# rtmi.net
KiCad netlist of a schematic drawn in EAGLE
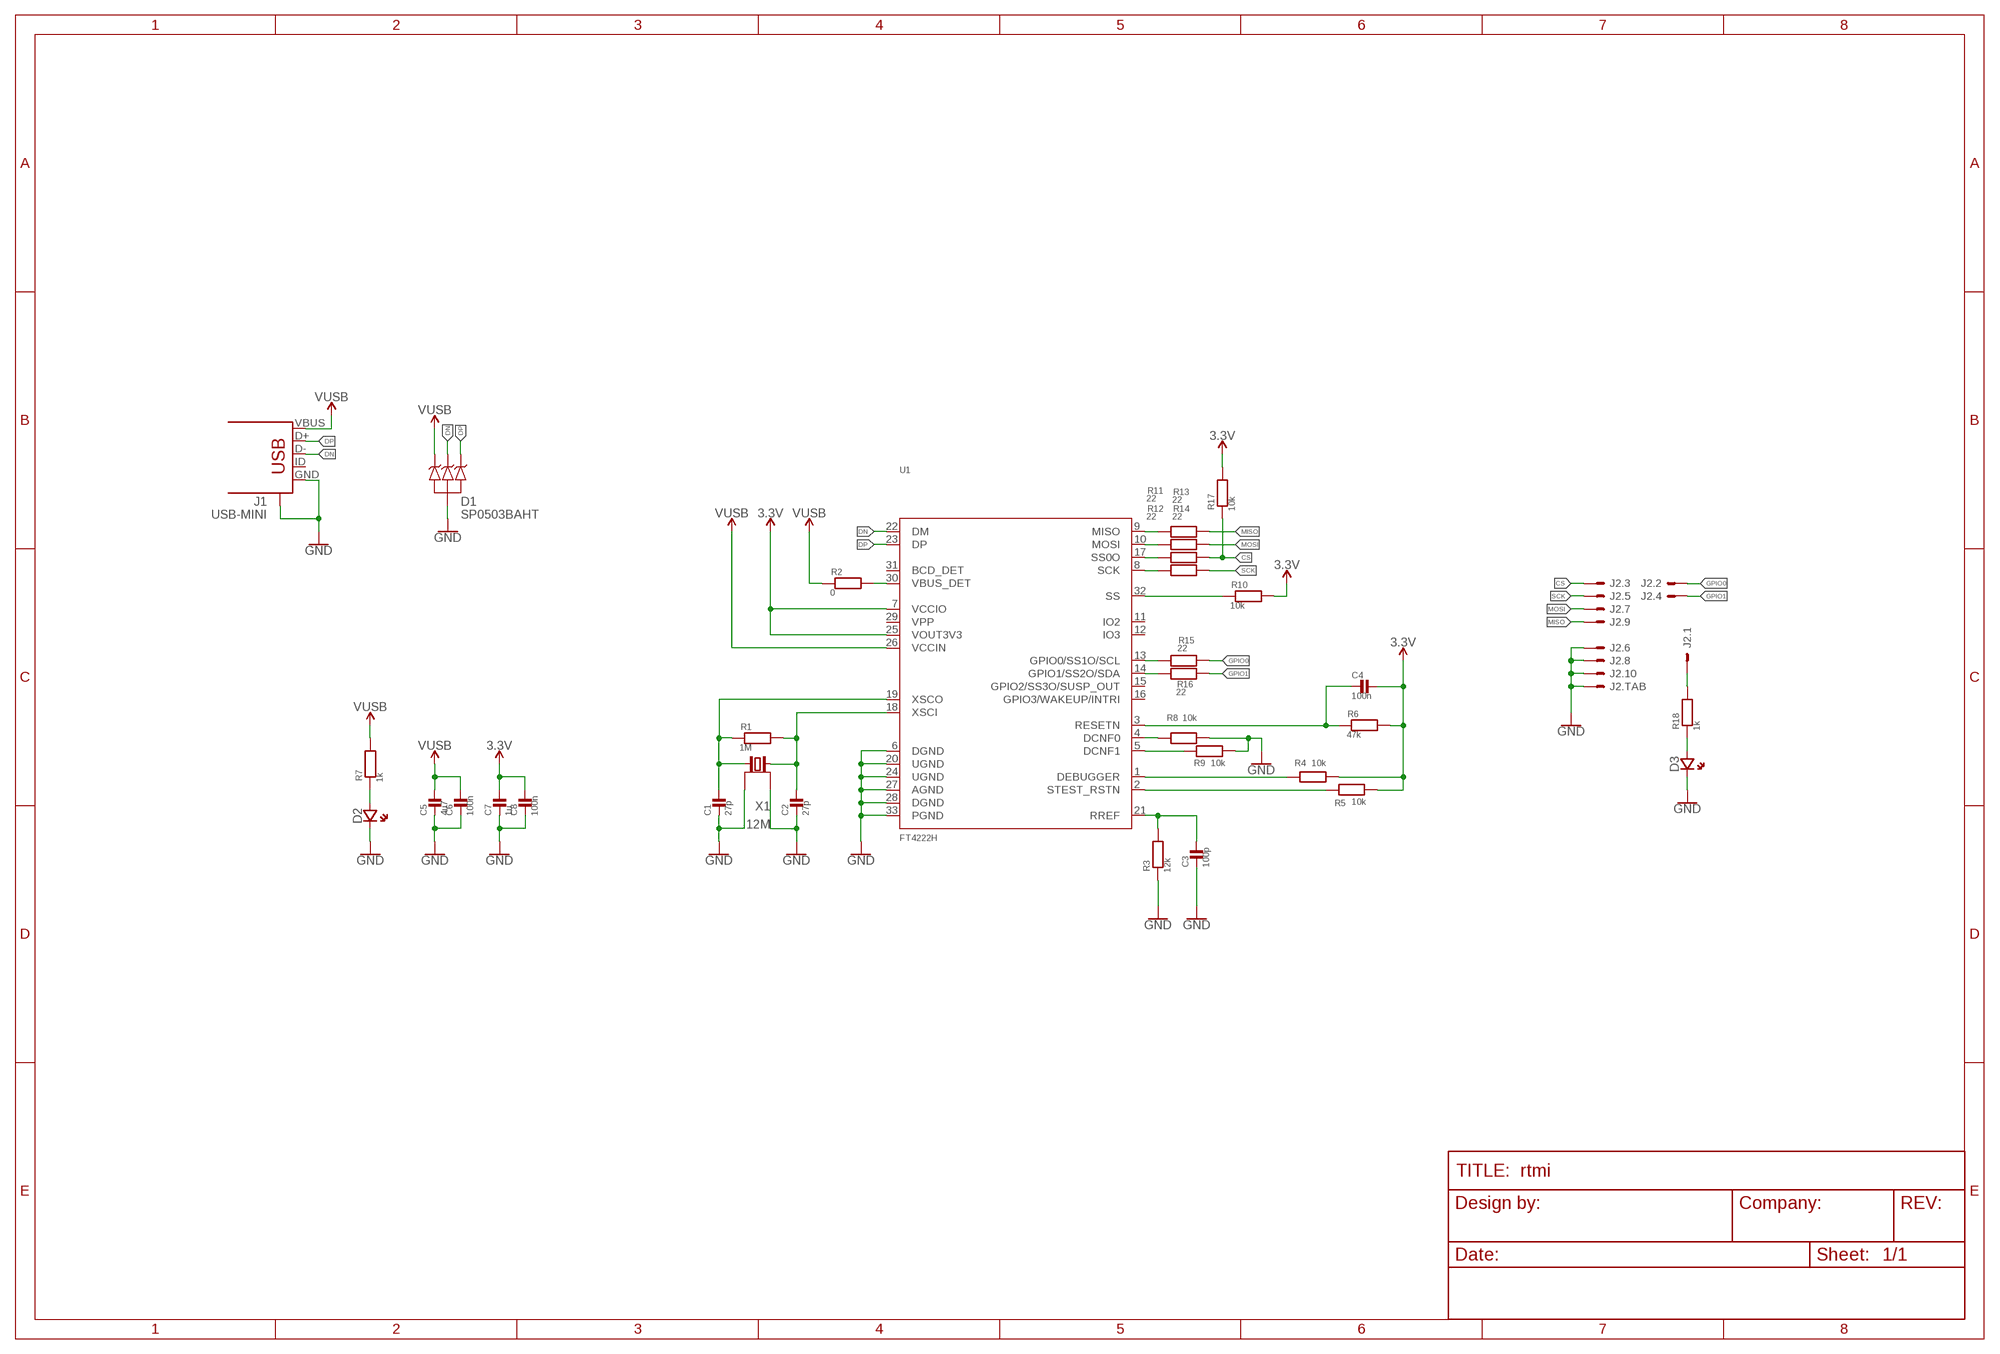
[diagram p0: schematic, sheet 1]

(export (version "E")
  (design (tool "Eeschema 10.0.6"))
  (components
    (comp (ref "C1")
      (value "27p")
      (footprint "eagle-import:0603_WAVE")
      (libsource (lib "eagle-import") (part "MLCC0603"))
    )
    (comp (ref "C2")
      (value "27p")
      (footprint "eagle-import:0603_WAVE")
      (libsource (lib "eagle-import") (part "MLCC0603"))
    )
    (comp (ref "C3")
      (value "100p")
      (footprint "eagle-import:0603_WAVE")
      (libsource (lib "eagle-import") (part "MLCC0603"))
    )
    (comp (ref "C4")
      (value "100n")
      (footprint "eagle-import:0603_WAVE")
      (libsource (lib "eagle-import") (part "MLCC0603"))
    )
    (comp (ref "C5")
      (value "4u7")
      (footprint "eagle-import:0603_WAVE")
      (libsource (lib "eagle-import") (part "MLCC0603"))
    )
    (comp (ref "C6")
      (value "100n")
      (footprint "eagle-import:0603_WAVE")
      (libsource (lib "eagle-import") (part "MLCC0603"))
    )
    (comp (ref "C7")
      (value "1u")
      (footprint "eagle-import:0603_WAVE")
      (libsource (lib "eagle-import") (part "MLCC0603"))
    )
    (comp (ref "C8")
      (value "100n")
      (footprint "eagle-import:0603_WAVE")
      (libsource (lib "eagle-import") (part "MLCC0603"))
    )
    (comp (ref "D1")
      (value "SP0503BAHT")
      (footprint "eagle-import:SOT143")
      (libsource (lib "eagle-import") (part "SP0503BAHT"))
    )
    (comp (ref "D2")
      (value "LED0603")
      (footprint "eagle-import:CHIPLED_0603")
      (libsource (lib "eagle-import") (part "LED0603"))
    )
    (comp (ref "D3")
      (value "LED0603")
      (footprint "eagle-import:CHIPLED_0603")
      (libsource (lib "eagle-import") (part "LED0603"))
    )
    (comp (ref "J1")
      (value "USB-MINI")
      (footprint "eagle-import:USB-MINI-SMD")
      (libsource (lib "eagle-import") (part "USB-MINI"))
    )
    (comp (ref "J2")
      (value "F20F-10DP-1V")
      (footprint "eagle-import:F20F-10DP-1V")
      (libsource (lib "eagle-import") (part "F20F-10DP-1V"))
    )
    (comp (ref "R1")
      (value "1M")
      (footprint "eagle-import:0603_WAVE")
      (libsource (lib "eagle-import") (part "RESISTOR0603"))
    )
    (comp (ref "R2")
      (value "0")
      (footprint "eagle-import:0603_WAVE")
      (libsource (lib "eagle-import") (part "RESISTOR0603"))
    )
    (comp (ref "R3")
      (value "12k")
      (footprint "eagle-import:0603_WAVE")
      (libsource (lib "eagle-import") (part "RESISTOR0603"))
    )
    (comp (ref "R4")
      (value "10k")
      (footprint "eagle-import:0603_WAVE")
      (libsource (lib "eagle-import") (part "RESISTOR0603"))
    )
    (comp (ref "R5")
      (value "10k")
      (footprint "eagle-import:0603_WAVE")
      (libsource (lib "eagle-import") (part "RESISTOR0603"))
    )
    (comp (ref "R6")
      (value "47k")
      (footprint "eagle-import:0603_WAVE")
      (libsource (lib "eagle-import") (part "RESISTOR0603"))
    )
    (comp (ref "R7")
      (value "1k")
      (footprint "eagle-import:0603_WAVE")
      (libsource (lib "eagle-import") (part "RESISTOR0603"))
    )
    (comp (ref "R8")
      (value "10k")
      (footprint "eagle-import:0603_WAVE")
      (libsource (lib "eagle-import") (part "RESISTOR0603"))
    )
    (comp (ref "R9")
      (value "10k")
      (footprint "eagle-import:0603_WAVE")
      (libsource (lib "eagle-import") (part "RESISTOR0603"))
    )
    (comp (ref "R10")
      (value "10k")
      (footprint "eagle-import:0603_WAVE")
      (libsource (lib "eagle-import") (part "RESISTOR0603"))
    )
    (comp (ref "R11")
      (value "22")
      (footprint "eagle-import:0603_WAVE")
      (libsource (lib "eagle-import") (part "RESISTOR0603"))
    )
    (comp (ref "R12")
      (value "22")
      (footprint "eagle-import:0603_WAVE")
      (libsource (lib "eagle-import") (part "RESISTOR0603"))
    )
    (comp (ref "R13")
      (value "22")
      (footprint "eagle-import:0603_WAVE")
      (libsource (lib "eagle-import") (part "RESISTOR0603"))
    )
    (comp (ref "R14")
      (value "22")
      (footprint "eagle-import:0603_WAVE")
      (libsource (lib "eagle-import") (part "RESISTOR0603"))
    )
    (comp (ref "R15")
      (value "22")
      (footprint "eagle-import:0603_WAVE")
      (libsource (lib "eagle-import") (part "RESISTOR0603"))
    )
    (comp (ref "R16")
      (value "22")
      (footprint "eagle-import:0603_WAVE")
      (libsource (lib "eagle-import") (part "RESISTOR0603"))
    )
    (comp (ref "R17")
      (value "10k")
      (footprint "eagle-import:0603_WAVE")
      (libsource (lib "eagle-import") (part "RESISTOR0603"))
    )
    (comp (ref "R18")
      (value "1k")
      (footprint "eagle-import:0603_WAVE")
      (libsource (lib "eagle-import") (part "RESISTOR0603"))
    )
    (comp (ref "U1")
      (value "FT4222H")
      (footprint "eagle-import:QFN32")
      (libsource (lib "eagle-import") (part "FT4222H"))
    )
    (comp (ref "X1")
      (value "12M")
      (footprint "eagle-import:4-SMD-3225")
      (libsource (lib "eagle-import") (part "CRYSTAL_4P"))
    )
  )
  (nets
    (net (code "1") (name "3.3V") (class "Default")
      (node (ref "C4") (pin "P$1") (pinfunction "P$1_P$1") (pintype "bidirectional"))
      (node (ref "C7") (pin "P$1") (pinfunction "P$1_P$1") (pintype "bidirectional"))
      (node (ref "C8") (pin "P$1") (pinfunction "P$1_P$1") (pintype "bidirectional"))
      (node (ref "R10") (pin "P$2") (pinfunction "P$2_P$2") (pintype "bidirectional"))
      (node (ref "R17") (pin "P$2") (pinfunction "P$2_P$2") (pintype "bidirectional"))
      (node (ref "R4") (pin "P$2") (pinfunction "P$2_P$2") (pintype "bidirectional"))
      (node (ref "R5") (pin "P$2") (pinfunction "P$2_P$2") (pintype "bidirectional"))
      (node (ref "R6") (pin "P$2") (pinfunction "P$2_P$2") (pintype "bidirectional"))
      (node (ref "U1") (pin "25") (pinfunction "VOUT3V3_25") (pintype "bidirectional"))
      (node (ref "U1") (pin "7") (pinfunction "VCCIO_7") (pintype "bidirectional"))
    )
    (net (code "2") (name "CS") (class "Default")
      (node (ref "J2") (pin "3") (pinfunction "S_3") (pintype "passive"))
      (node (ref "R13") (pin "P$2") (pinfunction "P$2_P$2") (pintype "bidirectional"))
      (node (ref "R17") (pin "P$1") (pinfunction "P$1_P$1") (pintype "bidirectional"))
    )
    (net (code "3") (name "DN") (class "Default")
      (node (ref "D1") (pin "3") (pinfunction "3_3") (pintype "bidirectional"))
      (node (ref "J1") (pin "D-") (pinfunction "D-_D-") (pintype "bidirectional"))
      (node (ref "U1") (pin "22") (pinfunction "DM_22") (pintype "bidirectional"))
    )
    (net (code "4") (name "DP") (class "Default")
      (node (ref "D1") (pin "4") (pinfunction "4_4") (pintype "bidirectional"))
      (node (ref "J1") (pin "D+") (pinfunction "D+_D+") (pintype "bidirectional"))
      (node (ref "U1") (pin "23") (pinfunction "DP_23") (pintype "bidirectional"))
    )
    (net (code "5") (name "GND") (class "Default")
      (node (ref "C1") (pin "P$2") (pinfunction "P$2_P$2") (pintype "bidirectional"))
      (node (ref "C2") (pin "P$2") (pinfunction "P$2_P$2") (pintype "bidirectional"))
      (node (ref "C3") (pin "P$2") (pinfunction "P$2_P$2") (pintype "bidirectional"))
      (node (ref "C5") (pin "P$2") (pinfunction "P$2_P$2") (pintype "bidirectional"))
      (node (ref "C6") (pin "P$2") (pinfunction "P$2_P$2") (pintype "bidirectional"))
      (node (ref "C7") (pin "P$2") (pinfunction "P$2_P$2") (pintype "bidirectional"))
      (node (ref "C8") (pin "P$2") (pinfunction "P$2_P$2") (pintype "bidirectional"))
      (node (ref "D1") (pin "1") (pinfunction "1_1") (pintype "bidirectional"))
      (node (ref "D2") (pin "C") (pinfunction "CA_C") (pintype "bidirectional"))
      (node (ref "D3") (pin "C") (pinfunction "CA_C") (pintype "bidirectional"))
      (node (ref "J1") (pin "GND") (pinfunction "GND_GND") (pintype "bidirectional"))
      (node (ref "J1") (pin "GND@1") (pinfunction "CASE_GND@1") (pintype "bidirectional"))
      (node (ref "J1") (pin "GND@2") (pinfunction "CASE_GND@2") (pintype "bidirectional"))
      (node (ref "J1") (pin "GND@3") (pinfunction "CASE_GND@3") (pintype "bidirectional"))
      (node (ref "J1") (pin "GND@4") (pinfunction "CASE_GND@4") (pintype "bidirectional"))
      (node (ref "J2") (pin "10") (pinfunction "S_10") (pintype "passive"))
      (node (ref "J2") (pin "6") (pinfunction "S_6") (pintype "passive"))
      (node (ref "J2") (pin "8") (pinfunction "S_8") (pintype "passive"))
      (node (ref "J2") (pin "TAB1") (pinfunction "S_TAB1") (pintype "passive"))
      (node (ref "J2") (pin "TAB2") (pinfunction "S_TAB2") (pintype "passive"))
      (node (ref "R3") (pin "P$1") (pinfunction "P$1_P$1") (pintype "bidirectional"))
      (node (ref "R8") (pin "P$2") (pinfunction "P$2_P$2") (pintype "bidirectional"))
      (node (ref "R9") (pin "P$2") (pinfunction "P$2_P$2") (pintype "bidirectional"))
      (node (ref "U1") (pin "20") (pinfunction "UGND_20") (pintype "bidirectional"))
      (node (ref "U1") (pin "24") (pinfunction "UGND_24") (pintype "bidirectional"))
      (node (ref "U1") (pin "27") (pinfunction "AGND_27") (pintype "bidirectional"))
      (node (ref "U1") (pin "28") (pinfunction "DGND_28") (pintype "bidirectional"))
      (node (ref "U1") (pin "33") (pinfunction "PGND_33") (pintype "bidirectional"))
      (node (ref "U1") (pin "6") (pinfunction "DGND_6") (pintype "bidirectional"))
      (node (ref "X1") (pin "2") (pinfunction "GND_2") (pintype "passive"))
      (node (ref "X1") (pin "4") (pinfunction "GND_4") (pintype "passive"))
    )
    (net (code "6") (name "GPIO0") (class "Default")
      (node (ref "J2") (pin "2") (pinfunction "S_2") (pintype "passive"))
      (node (ref "R15") (pin "P$2") (pinfunction "P$2_P$2") (pintype "bidirectional"))
    )
    (net (code "7") (name "GPIO1") (class "Default")
      (node (ref "J2") (pin "4") (pinfunction "S_4") (pintype "passive"))
      (node (ref "R16") (pin "P$2") (pinfunction "P$2_P$2") (pintype "bidirectional"))
    )
    (net (code "8") (name "MISO") (class "Default")
      (node (ref "J2") (pin "9") (pinfunction "S_9") (pintype "passive"))
      (node (ref "R11") (pin "P$2") (pinfunction "P$2_P$2") (pintype "bidirectional"))
    )
    (net (code "9") (name "MOSI") (class "Default")
      (node (ref "J2") (pin "7") (pinfunction "S_7") (pintype "passive"))
      (node (ref "R12") (pin "P$2") (pinfunction "P$2_P$2") (pintype "bidirectional"))
    )
    (net (code "10") (name "Net-(D2-AN)") (class "Default")
      (node (ref "D2") (pin "A") (pinfunction "AN_A") (pintype "bidirectional"))
      (node (ref "R7") (pin "P$1") (pinfunction "P$1_P$1") (pintype "bidirectional"))
    )
    (net (code "11") (name "Net-(D3-AN)") (class "Default")
      (node (ref "D3") (pin "A") (pinfunction "AN_A") (pintype "bidirectional"))
      (node (ref "R18") (pin "P$1") (pinfunction "P$1_P$1") (pintype "bidirectional"))
    )
    (net (code "12") (name "Net-(J2A-S)") (class "Default")
      (node (ref "J2") (pin "1") (pinfunction "S_1") (pintype "passive"))
      (node (ref "R18") (pin "P$2") (pinfunction "P$2_P$2") (pintype "bidirectional"))
    )
    (net (code "13") (name "Net-(U1-DCNF0)") (class "Default")
      (node (ref "R8") (pin "P$1") (pinfunction "P$1_P$1") (pintype "bidirectional"))
      (node (ref "U1") (pin "4") (pinfunction "DCNF0_4") (pintype "bidirectional"))
    )
    (net (code "14") (name "Net-(U1-DCNF1)") (class "Default")
      (node (ref "R9") (pin "P$1") (pinfunction "P$1_P$1") (pintype "bidirectional"))
      (node (ref "U1") (pin "5") (pinfunction "DCNF1_5") (pintype "bidirectional"))
    )
    (net (code "15") (name "Net-(U1-DEBUGGER)") (class "Default")
      (node (ref "R4") (pin "P$1") (pinfunction "P$1_P$1") (pintype "bidirectional"))
      (node (ref "U1") (pin "1") (pinfunction "DEBUGGER_1") (pintype "bidirectional"))
    )
    (net (code "16") (name "Net-(U1-GPIO0{slash}SS1O{slash}SCL)") (class "Default")
      (node (ref "R15") (pin "P$1") (pinfunction "P$1_P$1") (pintype "bidirectional"))
      (node (ref "U1") (pin "13") (pinfunction "GPIO0/SS1O/SCL_13") (pintype "bidirectional"))
    )
    (net (code "17") (name "Net-(U1-GPIO1{slash}SS2O{slash}SDA)") (class "Default")
      (node (ref "R16") (pin "P$1") (pinfunction "P$1_P$1") (pintype "bidirectional"))
      (node (ref "U1") (pin "14") (pinfunction "GPIO1/SS2O/SDA_14") (pintype "bidirectional"))
    )
    (net (code "18") (name "Net-(U1-MISO)") (class "Default")
      (node (ref "R11") (pin "P$1") (pinfunction "P$1_P$1") (pintype "bidirectional"))
      (node (ref "U1") (pin "9") (pinfunction "MISO_9") (pintype "bidirectional"))
    )
    (net (code "19") (name "Net-(U1-MOSI)") (class "Default")
      (node (ref "R12") (pin "P$1") (pinfunction "P$1_P$1") (pintype "bidirectional"))
      (node (ref "U1") (pin "10") (pinfunction "MOSI_10") (pintype "bidirectional"))
    )
    (net (code "20") (name "Net-(U1-RESETN)") (class "Default")
      (node (ref "C4") (pin "P$2") (pinfunction "P$2_P$2") (pintype "bidirectional"))
      (node (ref "R6") (pin "P$1") (pinfunction "P$1_P$1") (pintype "bidirectional"))
      (node (ref "U1") (pin "3") (pinfunction "RESETN_3") (pintype "bidirectional"))
    )
    (net (code "21") (name "Net-(U1-RREF)") (class "Default")
      (node (ref "C3") (pin "P$1") (pinfunction "P$1_P$1") (pintype "bidirectional"))
      (node (ref "R3") (pin "P$2") (pinfunction "P$2_P$2") (pintype "bidirectional"))
      (node (ref "U1") (pin "21") (pinfunction "RREF_21") (pintype "bidirectional"))
    )
    (net (code "22") (name "Net-(U1-SCK)") (class "Default")
      (node (ref "R14") (pin "P$1") (pinfunction "P$1_P$1") (pintype "bidirectional"))
      (node (ref "U1") (pin "8") (pinfunction "SCK_8") (pintype "bidirectional"))
    )
    (net (code "23") (name "Net-(U1-SS)") (class "Default")
      (node (ref "R10") (pin "P$1") (pinfunction "P$1_P$1") (pintype "bidirectional"))
      (node (ref "U1") (pin "32") (pinfunction "SS_32") (pintype "bidirectional"))
    )
    (net (code "24") (name "Net-(U1-SS0O)") (class "Default")
      (node (ref "R13") (pin "P$1") (pinfunction "P$1_P$1") (pintype "bidirectional"))
      (node (ref "U1") (pin "17") (pinfunction "SS0O_17") (pintype "bidirectional"))
    )
    (net (code "25") (name "Net-(U1-STEST_RSTN)") (class "Default")
      (node (ref "R5") (pin "P$1") (pinfunction "P$1_P$1") (pintype "bidirectional"))
      (node (ref "U1") (pin "2") (pinfunction "STEST_RSTN_2") (pintype "bidirectional"))
    )
    (net (code "26") (name "Net-(U1-VBUS_DET)") (class "Default")
      (node (ref "R2") (pin "P$2") (pinfunction "P$2_P$2") (pintype "bidirectional"))
      (node (ref "U1") (pin "30") (pinfunction "VBUS_DET_30") (pintype "bidirectional"))
    )
    (net (code "27") (name "Net-(U1-XSCI)") (class "Default")
      (node (ref "C2") (pin "P$1") (pinfunction "P$1_P$1") (pintype "bidirectional"))
      (node (ref "R1") (pin "P$2") (pinfunction "P$2_P$2") (pintype "bidirectional"))
      (node (ref "U1") (pin "18") (pinfunction "XSCI_18") (pintype "bidirectional"))
      (node (ref "X1") (pin "1") (pinfunction "1_1") (pintype "passive"))
    )
    (net (code "28") (name "Net-(U1-XSCO)") (class "Default")
      (node (ref "C1") (pin "P$1") (pinfunction "P$1_P$1") (pintype "bidirectional"))
      (node (ref "R1") (pin "P$1") (pinfunction "P$1_P$1") (pintype "bidirectional"))
      (node (ref "U1") (pin "19") (pinfunction "XSCO_19") (pintype "bidirectional"))
      (node (ref "X1") (pin "3") (pinfunction "2_3") (pintype "passive"))
    )
    (net (code "29") (name "SCK") (class "Default")
      (node (ref "J2") (pin "5") (pinfunction "S_5") (pintype "passive"))
      (node (ref "R14") (pin "P$2") (pinfunction "P$2_P$2") (pintype "bidirectional"))
    )
    (net (code "30") (name "VUSB") (class "Default")
      (node (ref "C5") (pin "P$1") (pinfunction "P$1_P$1") (pintype "bidirectional"))
      (node (ref "C6") (pin "P$1") (pinfunction "P$1_P$1") (pintype "bidirectional"))
      (node (ref "D1") (pin "2") (pinfunction "2_2") (pintype "bidirectional"))
      (node (ref "J1") (pin "VBUS") (pinfunction "VBUS_VBUS") (pintype "bidirectional"))
      (node (ref "R2") (pin "P$1") (pinfunction "P$1_P$1") (pintype "bidirectional"))
      (node (ref "R7") (pin "P$2") (pinfunction "P$2_P$2") (pintype "bidirectional"))
      (node (ref "U1") (pin "26") (pinfunction "VCCIN_26") (pintype "bidirectional"))
    )
    (net (code "31") (name "unconnected-(J1-PadID)") (class "Default")
      (node (ref "J1") (pin "ID") (pinfunction "ID_ID") (pintype "bidirectional"))
    )
    (net (code "32") (name "unconnected-(U1-BCD_DET-Pad31)") (class "Default")
      (node (ref "U1") (pin "31") (pinfunction "BCD_DET_31") (pintype "bidirectional"))
    )
    (net (code "33") (name "unconnected-(U1-GPIO2{slash}SS3O{slash}SUSP_OUT-Pad15)") (class "Default")
      (node (ref "U1") (pin "15") (pinfunction "GPIO2/SS3O/SUSP_OUT_15") (pintype "bidirectional"))
    )
    (net (code "34") (name "unconnected-(U1-GPIO3{slash}WAKEUP{slash}INTRI-Pad16)") (class "Default")
      (node (ref "U1") (pin "16") (pinfunction "GPIO3/WAKEUP/INTRI_16") (pintype "bidirectional"))
    )
    (net (code "35") (name "unconnected-(U1-IO2-Pad11)") (class "Default")
      (node (ref "U1") (pin "11") (pinfunction "IO2_11") (pintype "bidirectional"))
    )
    (net (code "36") (name "unconnected-(U1-IO3-Pad12)") (class "Default")
      (node (ref "U1") (pin "12") (pinfunction "IO3_12") (pintype "bidirectional"))
    )
    (net (code "37") (name "unconnected-(U1-VPP-Pad29)") (class "Default")
      (node (ref "U1") (pin "29") (pinfunction "VPP_29") (pintype "bidirectional"))
    )
  )
)
